# digital_host_for_ADS1216_SPI_connecor_to.net
KiCad netlist of a schematic drawn in Altium Designer
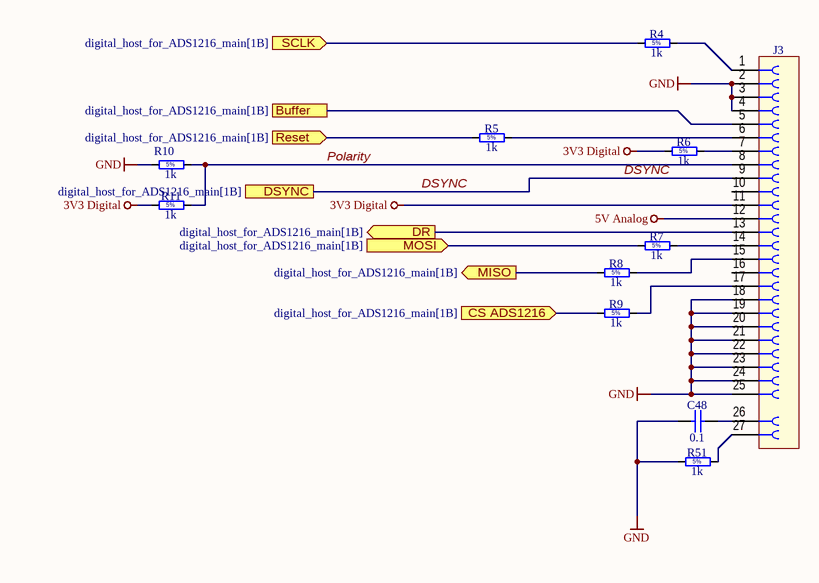
[diagram p0: digital_host_for_ADS1216_SPI_connecor_to_ADS1216.SchDoc]

(export (version "E")
  (design (tool "Eeschema 10.0.6"))
  (components
    (comp (ref "C48")
      (value "0.1")
      (footprint "CAPC2012X90N")
      (description "Non-polarised capacitor2012")
      (libsource (lib "schematic_hall_library") (part "Capacitor - non polarized"))
    )
    (comp (ref "J3")
      (value "~")
      (footprint "footprint_library:TYCO_3-1634586-2")
      (description "Connector 25 Female")
      (libsource (lib "first_scheme.~(65)") (part "Connector 25 Female"))
    )
    (comp (ref "R4")
      (value "1k")
      (footprint "RESC2012X70N")
      (description "Resistor - 5%")
      (fields (field (name "TOLERANCE") "5%"))
      (libsource (lib "first_scheme.~(65)") (part "Resistor - 5%"))
    )
    (comp (ref "R5")
      (value "1k")
      (footprint "RESC2012X70N")
      (description "Resistor - 5%")
      (fields (field (name "TOLERANCE") "5%"))
      (libsource (lib "first_scheme.~(65)") (part "Resistor - 5%"))
    )
    (comp (ref "R6")
      (value "1k")
      (footprint "RESC2012X70N")
      (description "Resistor - 5%")
      (fields (field (name "TOLERANCE") "5%"))
      (libsource (lib "first_scheme.~(65)") (part "Resistor - 5%"))
    )
    (comp (ref "R7")
      (value "1k")
      (footprint "RESC2012X70N")
      (description "Resistor - 5%")
      (fields (field (name "TOLERANCE") "5%"))
      (libsource (lib "first_scheme.~(65)") (part "Resistor - 5%"))
    )
    (comp (ref "R8")
      (value "1k")
      (footprint "RESC2012X70N")
      (description "Resistor - 5%")
      (fields (field (name "TOLERANCE") "5%"))
      (libsource (lib "first_scheme.~(65)") (part "Resistor - 5%"))
    )
    (comp (ref "R9")
      (value "1k")
      (footprint "RESC2012X70N")
      (description "Resistor - 5%")
      (fields (field (name "TOLERANCE") "5%"))
      (libsource (lib "first_scheme.~(65)") (part "Resistor - 5%"))
    )
    (comp (ref "R10")
      (value "1k")
      (footprint "RESC2012X70N")
      (description "Resistor - 5%")
      (fields (field (name "TOLERANCE") "5%"))
      (libsource (lib "first_scheme.~(65)") (part "Resistor - 5%"))
    )
    (comp (ref "R11")
      (value "1k")
      (footprint "RESC2012X70N")
      (description "Resistor - 5%")
      (fields (field (name "TOLERANCE") "5%"))
      (libsource (lib "first_scheme.~(65)") (part "Resistor - 5%"))
    )
    (comp (ref "R51")
      (value "1k")
      (footprint "RESC2012X70N")
      (description "Resistor - 5%")
      (fields (field (name "TOLERANCE") "5%"))
      (libsource (lib "Integrated_Library1") (part "Resistor - 5%"))
    )
  )
  (nets
    (net (code "1") (name "/Buffer") (class "Default")
      (node (ref "J3") (pin "5") (pinfunction "5_5") (pintype "passive"))
    )
    (net (code "2") (name "/CS ADS1216") (class "Default")
      (node (ref "R9") (pin "1") (pinfunction "1_1") (pintype "passive"))
    )
    (net (code "3") (name "/DR") (class "Default")
      (node (ref "J3") (pin "13") (pinfunction "13_13") (pintype "passive"))
    )
    (net (code "4") (name "/DSYNC") (class "Default")
      (node (ref "J3") (pin "9") (pinfunction "9_9") (pintype "passive"))
    )
    (net (code "5") (name "/MISO") (class "Default")
      (node (ref "R8") (pin "1") (pinfunction "1_1") (pintype "passive"))
    )
    (net (code "6") (name "/MOSI") (class "Default")
      (node (ref "R7") (pin "1") (pinfunction "1_1") (pintype "passive"))
    )
    (net (code "7") (name "/Polarity") (class "Default")
      (node (ref "J3") (pin "8") (pinfunction "8_8") (pintype "passive"))
      (node (ref "R10") (pin "1") (pinfunction "1_1") (pintype "passive"))
      (node (ref "R11") (pin "1") (pinfunction "1_1") (pintype "passive"))
    )
    (net (code "8") (name "/Reset") (class "Default")
      (node (ref "R5") (pin "1") (pinfunction "1_1") (pintype "passive"))
    )
    (net (code "9") (name "/SCLK") (class "Default")
      (node (ref "R4") (pin "1") (pinfunction "1_1") (pintype "passive"))
    )
    (net (code "10") (name "3V3 Digital") (class "Default")
      (node (ref "J3") (pin "11") (pinfunction "11_11") (pintype "passive"))
      (node (ref "R11") (pin "2") (pinfunction "2_2") (pintype "passive"))
      (node (ref "R6") (pin "1") (pinfunction "1_1") (pintype "passive"))
    )
    (net (code "11") (name "5V Analog") (class "Default")
      (node (ref "J3") (pin "12") (pinfunction "12_12") (pintype "passive"))
    )
    (net (code "12") (name "GND") (class "Default")
      (node (ref "C48") (pin "1") (pinfunction "1_1") (pintype "passive"))
      (node (ref "J3") (pin "18") (pinfunction "18_18") (pintype "passive"))
      (node (ref "J3") (pin "19") (pinfunction "19_19") (pintype "passive"))
      (node (ref "J3") (pin "2") (pinfunction "2_2") (pintype "passive"))
      (node (ref "J3") (pin "20") (pinfunction "20_20") (pintype "passive"))
      (node (ref "J3") (pin "21") (pinfunction "21_21") (pintype "passive"))
      (node (ref "J3") (pin "22") (pinfunction "22_22") (pintype "passive"))
      (node (ref "J3") (pin "23") (pinfunction "23_23") (pintype "passive"))
      (node (ref "J3") (pin "24") (pinfunction "24_24") (pintype "passive"))
      (node (ref "J3") (pin "25") (pinfunction "25_25") (pintype "passive"))
      (node (ref "J3") (pin "3") (pinfunction "3_3") (pintype "passive"))
      (node (ref "J3") (pin "4") (pinfunction "4_4") (pintype "passive"))
      (node (ref "R10") (pin "2") (pinfunction "2_2") (pintype "passive"))
      (node (ref "R51") (pin "1") (pinfunction "1_1") (pintype "passive"))
    )
    (net (code "13") (name "Net-(C48-Pad2)") (class "Default")
      (node (ref "C48") (pin "2") (pinfunction "2_2") (pintype "passive"))
      (node (ref "J3") (pin "26") (pinfunction "26_26") (pintype "passive"))
    )
    (net (code "14") (name "Net-(J3-Pad1)") (class "Default")
      (node (ref "J3") (pin "1") (pinfunction "1_1") (pintype "passive"))
      (node (ref "R4") (pin "2") (pinfunction "2_2") (pintype "passive"))
    )
    (net (code "15") (name "Net-(J3-Pad6)") (class "Default")
      (node (ref "J3") (pin "6") (pinfunction "6_6") (pintype "passive"))
      (node (ref "R5") (pin "2") (pinfunction "2_2") (pintype "passive"))
    )
    (net (code "16") (name "Net-(J3-Pad7)") (class "Default")
      (node (ref "J3") (pin "7") (pinfunction "7_7") (pintype "passive"))
      (node (ref "R6") (pin "2") (pinfunction "2_2") (pintype "passive"))
    )
    (net (code "17") (name "Net-(J3-Pad14)") (class "Default")
      (node (ref "J3") (pin "14") (pinfunction "14_14") (pintype "passive"))
      (node (ref "R7") (pin "2") (pinfunction "2_2") (pintype "passive"))
    )
    (net (code "18") (name "Net-(J3-Pad15)") (class "Default")
      (node (ref "J3") (pin "15") (pinfunction "15_15") (pintype "passive"))
      (node (ref "R8") (pin "2") (pinfunction "2_2") (pintype "passive"))
    )
    (net (code "19") (name "Net-(J3-Pad17)") (class "Default")
      (node (ref "J3") (pin "17") (pinfunction "17_17") (pintype "passive"))
      (node (ref "R9") (pin "2") (pinfunction "2_2") (pintype "passive"))
    )
    (net (code "20") (name "Net-(J3-Pad27)") (class "Default")
      (node (ref "J3") (pin "27") (pinfunction "27_27") (pintype "passive"))
      (node (ref "R51") (pin "2") (pinfunction "2_2") (pintype "passive"))
    )
    (net (code "21") (name "unconnected-(J3-Pad10)") (class "Default")
      (node (ref "J3") (pin "10") (pinfunction "10_10") (pintype "passive"))
    )
    (net (code "22") (name "unconnected-(J3-Pad16)") (class "Default")
      (node (ref "J3") (pin "16") (pinfunction "16_16") (pintype "passive"))
    )
  )
)
